# Power_Line_24V.net
KiCad netlist of a schematic drawn in Altium Designer
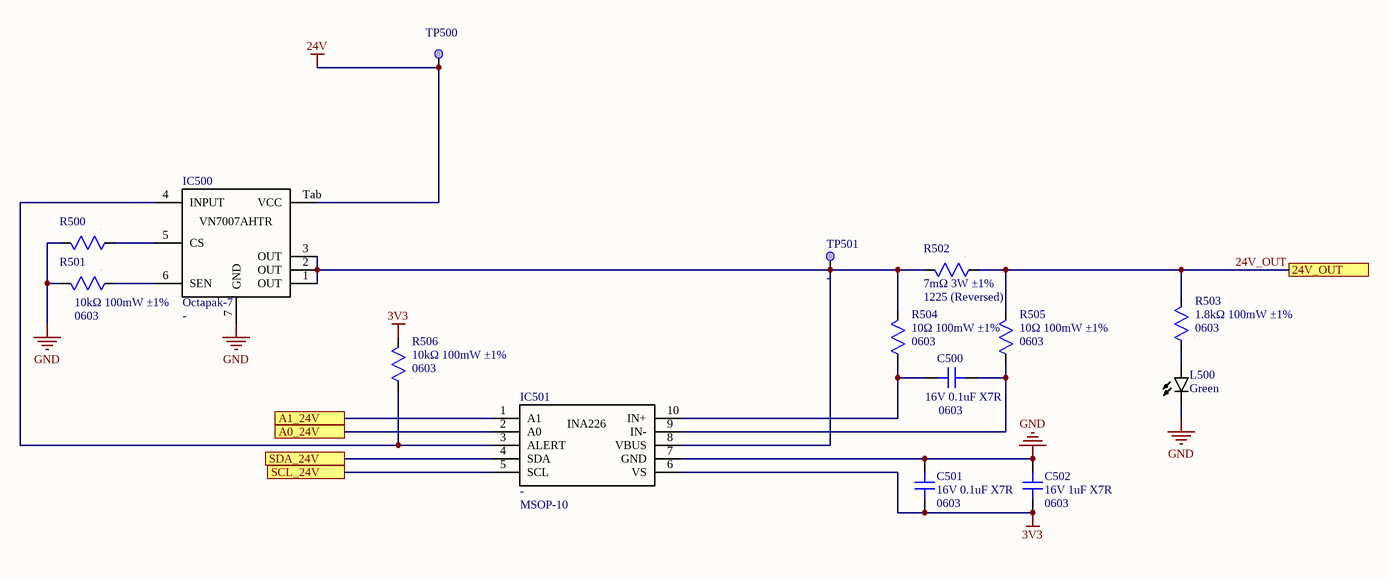
[diagram p0: Power_Line_24V.SchDoc]

(export (version "E")
  (design (tool "Eeschema 10.0.6"))
  (components
    (comp (ref "C500")
      (value "16V 0.1uF X7R")
      (footprint "CAP SMD 0603")
      (description "Condensadores de cerámica multicapa (MLCC- SMD/SMT) WCAP-CSGP 0.1uF 0603 10% 16V MLCC")
      (fields
        (field (name "PACKAGE") "0603")
        (field (name "MPN") "885012206046")
        (field (name "MANUFACTURER") "Wurth Elektronik")
      )
      (libsource (lib "eUSR_Database") (part "CAP non polarized"))
    )
    (comp (ref "C501")
      (value "16V 0.1uF X7R")
      (footprint "CAP SMD 0603")
      (description "Condensadores de cerámica multicapa (MLCC- SMD/SMT) WCAP-CSGP 0.1uF 0603 10% 16V MLCC")
      (fields
        (field (name "PACKAGE") "0603")
        (field (name "MPN") "885012206046")
        (field (name "MANUFACTURER") "Wurth Elektronik")
      )
      (libsource (lib "eUSR_Database") (part "CAP non polarized"))
    )
    (comp (ref "C502")
      (value "16V 1uF X7R")
      (footprint "CAP SMD 0603")
      (description "Condensadores de cerámica multicapa (MLCC- SMD/SMT) WCAP-CSGP 1uF 0603 10% 16V MLCC")
      (fields
        (field (name "PACKAGE") "0603")
        (field (name "MPN") "885012206052")
        (field (name "MANUFACTURER") "Wurth Elektronik")
      )
      (libsource (lib "eUSR_Database") (part "CAP non polarized"))
    )
    (comp (ref "IC500")
      (value "-")
      (footprint "Octapak-7")
      (fields
        (field (name "PACKAGE") "Octapak-7")
        (field (name "MPN") "VN7007AHTR")
        (field (name "MANUFACTURER") "511-VN7007AHTR")
      )
      (libsource (lib "eUSR_Database") (part "VN7007AHTR"))
    )
    (comp (ref "IC501")
      (value "-")
      (footprint "VSOP-10")
      (fields
        (field (name "PACKAGE") "MSOP-10")
        (field (name "MPN") "INA226AIDGSR")
        (field (name "MANUFACTURER") "595-INA226AIDGSR")
        (field (name "Comment") "INA226")
      )
      (libsource (lib "eUSR_Database") (part "INA226"))
    )
    (comp (ref "L500")
      (value "Green")
      (footprint "LED SMD 0603")
      (description "LED de un solo color Green 525nm 1400mcd 2.85V 73deg 0603")
      (fields (field (name "MPN") "VLMTG1400-GS08") (field (name "MANUFACTURER") "Vishay Semiconductors"))
      (libsource (lib "eUSR_Database") (part "LED WHITE"))
    )
    (comp (ref "R500")
      (value "RES")
      (footprint "RES SMD 0603")
      (description "Resistores de película gruesa - SMD WRIS-RSKS 10 kOhms 1 % 0.1 W 0603 AEC-Q200")
      (fields (field (name "MPN") "560112116005") (field (name "MANUFACTURER") "Wurth Elektronik"))
      (libsource (lib "eUSR_Database") (part "RES"))
    )
    (comp (ref "R501")
      (value "10kΩ 100mW ±1%")
      (footprint "RES SMD 0603")
      (description "Resistores de película gruesa - SMD WRIS-RSKS 10 kOhms 1 % 0.1 W 0603 AEC-Q200")
      (fields
        (field (name "PACKAGE") "0603")
        (field (name "MPN") "560112116005")
        (field (name "MANUFACTURER") "Wurth Elektronik")
      )
      (libsource (lib "eUSR_Database") (part "RES"))
    )
    (comp (ref "R502")
      (value "7mΩ 3W ±1%")
      (footprint "RES SMD 1225 Reversed")
      (description "Resistores de detección de corriente - SMD 3W 0.007ohm 1% 50ppm")
      (fields
        (field (name "PACKAGE") "1225 (Reversed)")
        (field (name "MPN") "KRL6432E-M-R007-F-T1")
        (field (name "MANUFACTURER") "Susumu")
      )
      (libsource (lib "eUSR_Database") (part "RES"))
    )
    (comp (ref "R503")
      (value "1.8kΩ 100mW ±1%")
      (footprint "RES SMD 0603")
      (description "Resistores de película gruesa - SMD WRIS-RSKS 1.8 kOhms 1 % 0.1 W 0603 AEC-Q200")
      (fields
        (field (name "PACKAGE") "0603")
        (field (name "MPN") "560112116032")
        (field (name "MANUFACTURER") "Wurth Elektronik")
      )
      (libsource (lib "eUSR_Database") (part "RES"))
    )
    (comp (ref "R504")
      (value "10Ω 100mW ±1%")
      (footprint "RES SMD 0603")
      (description "Resistores de película gruesa - SMD WRIS-RSKS 10 Ohms 1 % 0.1 W 0603 AEC-Q200")
      (fields
        (field (name "PACKAGE") "0603")
        (field (name "MPN") "560112116013")
        (field (name "MANUFACTURER") "Wurth Elektronik")
      )
      (libsource (lib "eUSR_Database") (part "RES"))
    )
    (comp (ref "R505")
      (value "10Ω 100mW ±1%")
      (footprint "RES SMD 0603")
      (description "Resistores de película gruesa - SMD WRIS-RSKS 10 Ohms 1 % 0.1 W 0603 AEC-Q200")
      (fields
        (field (name "PACKAGE") "0603")
        (field (name "MPN") "560112116013")
        (field (name "MANUFACTURER") "Wurth Elektronik")
      )
      (libsource (lib "eUSR_Database") (part "RES"))
    )
    (comp (ref "R506")
      (value "10kΩ 100mW ±1%")
      (footprint "RES SMD 0603")
      (description "Resistores de película gruesa - SMD WRIS-RSKS 10 kOhms 1 % 0.1 W 0603 AEC-Q200")
      (fields
        (field (name "PACKAGE") "0603")
        (field (name "MPN") "560112116005")
        (field (name "MANUFACTURER") "Wurth Elektronik")
      )
      (libsource (lib "eUSR_Database") (part "RES"))
    )
    (comp (ref "TP500")
      (value "Test Point")
      (footprint "TP_THT_1.5MM")
      (description "Test Point 1.5mm THT")
      (libsource (lib "eUSR_Database") (part "TP"))
    )
    (comp (ref "TP501")
      (value "-")
      (footprint "TP_SMD_1MM")
      (description "Test Point")
      (libsource (lib "eUSR_Database") (part "TP1mm"))
    )
  )
  (nets
    (net (code "1") (name "/24V_OUT") (class "Default")
      (node (ref "R502") (pin "1") (pinfunction "1_1") (pintype "passive"))
      (node (ref "R503") (pin "2") (pinfunction "2_2") (pintype "passive"))
      (node (ref "R505") (pin "2") (pinfunction "2_2") (pintype "passive"))
    )
    (net (code "2") (name "/A0_24V") (class "Default")
      (node (ref "IC501") (pin "2") (pinfunction "A0_2") (pintype "passive"))
    )
    (net (code "3") (name "/A1_24V") (class "Default")
      (node (ref "IC501") (pin "1") (pinfunction "A1_1") (pintype "passive"))
    )
    (net (code "4") (name "/SCL_24V") (class "Default")
      (node (ref "IC501") (pin "5") (pinfunction "SCL_5") (pintype "passive"))
    )
    (net (code "5") (name "/SDA_24V") (class "Default")
      (node (ref "IC501") (pin "4") (pinfunction "SDA_4") (pintype "passive"))
    )
    (net (code "6") (name "3V3") (class "Default")
      (node (ref "C501") (pin "2") (pinfunction "2_2") (pintype "passive"))
      (node (ref "C502") (pin "2") (pinfunction "2_2") (pintype "passive"))
      (node (ref "IC501") (pin "6") (pinfunction "VS_6") (pintype "passive"))
      (node (ref "R506") (pin "2") (pinfunction "2_2") (pintype "passive"))
    )
    (net (code "7") (name "24V") (class "Default")
      (node (ref "IC500") (pin "Tab") (pinfunction "VCC_Tab") (pintype "passive"))
      (node (ref "TP500") (pin "1") (pinfunction "1_1") (pintype "passive"))
    )
    (net (code "8") (name "GND") (class "Default")
      (node (ref "C501") (pin "1") (pinfunction "1_1") (pintype "passive"))
      (node (ref "C502") (pin "1") (pinfunction "1_1") (pintype "passive"))
      (node (ref "IC500") (pin "7") (pinfunction "GND_7") (pintype "passive"))
      (node (ref "IC501") (pin "7") (pinfunction "GND_7") (pintype "passive"))
      (node (ref "L500") (pin "C") (pinfunction "C_C") (pintype "passive"))
      (node (ref "R500") (pin "2") (pinfunction "2_2") (pintype "passive"))
      (node (ref "R501") (pin "2") (pinfunction "2_2") (pintype "passive"))
    )
    (net (code "9") (name "Net-(IC500-CS)") (class "Default")
      (node (ref "IC500") (pin "5") (pinfunction "CS_5") (pintype "passive"))
      (node (ref "R500") (pin "1") (pinfunction "1_1") (pintype "passive"))
    )
    (net (code "10") (name "Net-(IC500-INPUT)") (class "Default")
      (node (ref "IC500") (pin "4") (pinfunction "INPUT_4") (pintype "passive"))
      (node (ref "IC501") (pin "3") (pinfunction "ALERT_3") (pintype "passive"))
      (node (ref "R506") (pin "1") (pinfunction "1_1") (pintype "passive"))
    )
    (net (code "11") (name "Net-(IC500-SEN)") (class "Default")
      (node (ref "IC500") (pin "6") (pinfunction "SEN_6") (pintype "passive"))
      (node (ref "R501") (pin "1") (pinfunction "1_1") (pintype "passive"))
    )
    (net (code "12") (name "Net-(IC501-IN+)") (class "Default")
      (node (ref "C500") (pin "1") (pinfunction "1_1") (pintype "passive"))
      (node (ref "IC501") (pin "10") (pinfunction "IN+_10") (pintype "passive"))
      (node (ref "R504") (pin "1") (pinfunction "1_1") (pintype "passive"))
    )
    (net (code "13") (name "Net-(IC501-IN-)") (class "Default")
      (node (ref "C500") (pin "2") (pinfunction "2_2") (pintype "passive"))
      (node (ref "IC501") (pin "9") (pinfunction "IN-_9") (pintype "passive"))
      (node (ref "R505") (pin "1") (pinfunction "1_1") (pintype "passive"))
    )
    (net (code "14") (name "Net-(IC501-VBUS)") (class "Default")
      (node (ref "IC500") (pin "1") (pinfunction "OUT_1") (pintype "passive"))
      (node (ref "IC500") (pin "2") (pinfunction "OUT_2") (pintype "passive"))
      (node (ref "IC500") (pin "3") (pinfunction "OUT_3") (pintype "passive"))
      (node (ref "IC501") (pin "8") (pinfunction "VBUS_8") (pintype "passive"))
      (node (ref "R502") (pin "2") (pinfunction "2_2") (pintype "passive"))
      (node (ref "R504") (pin "2") (pinfunction "2_2") (pintype "passive"))
      (node (ref "TP501") (pin "1") (pinfunction "1_1") (pintype "passive"))
    )
    (net (code "15") (name "Net-(L500-PadA)") (class "Default")
      (node (ref "L500") (pin "A") (pinfunction "A_A") (pintype "passive"))
      (node (ref "R503") (pin "1") (pinfunction "1_1") (pintype "passive"))
    )
  )
)
